# MUL.net
KiCad netlist of a schematic drawn in EAGLE
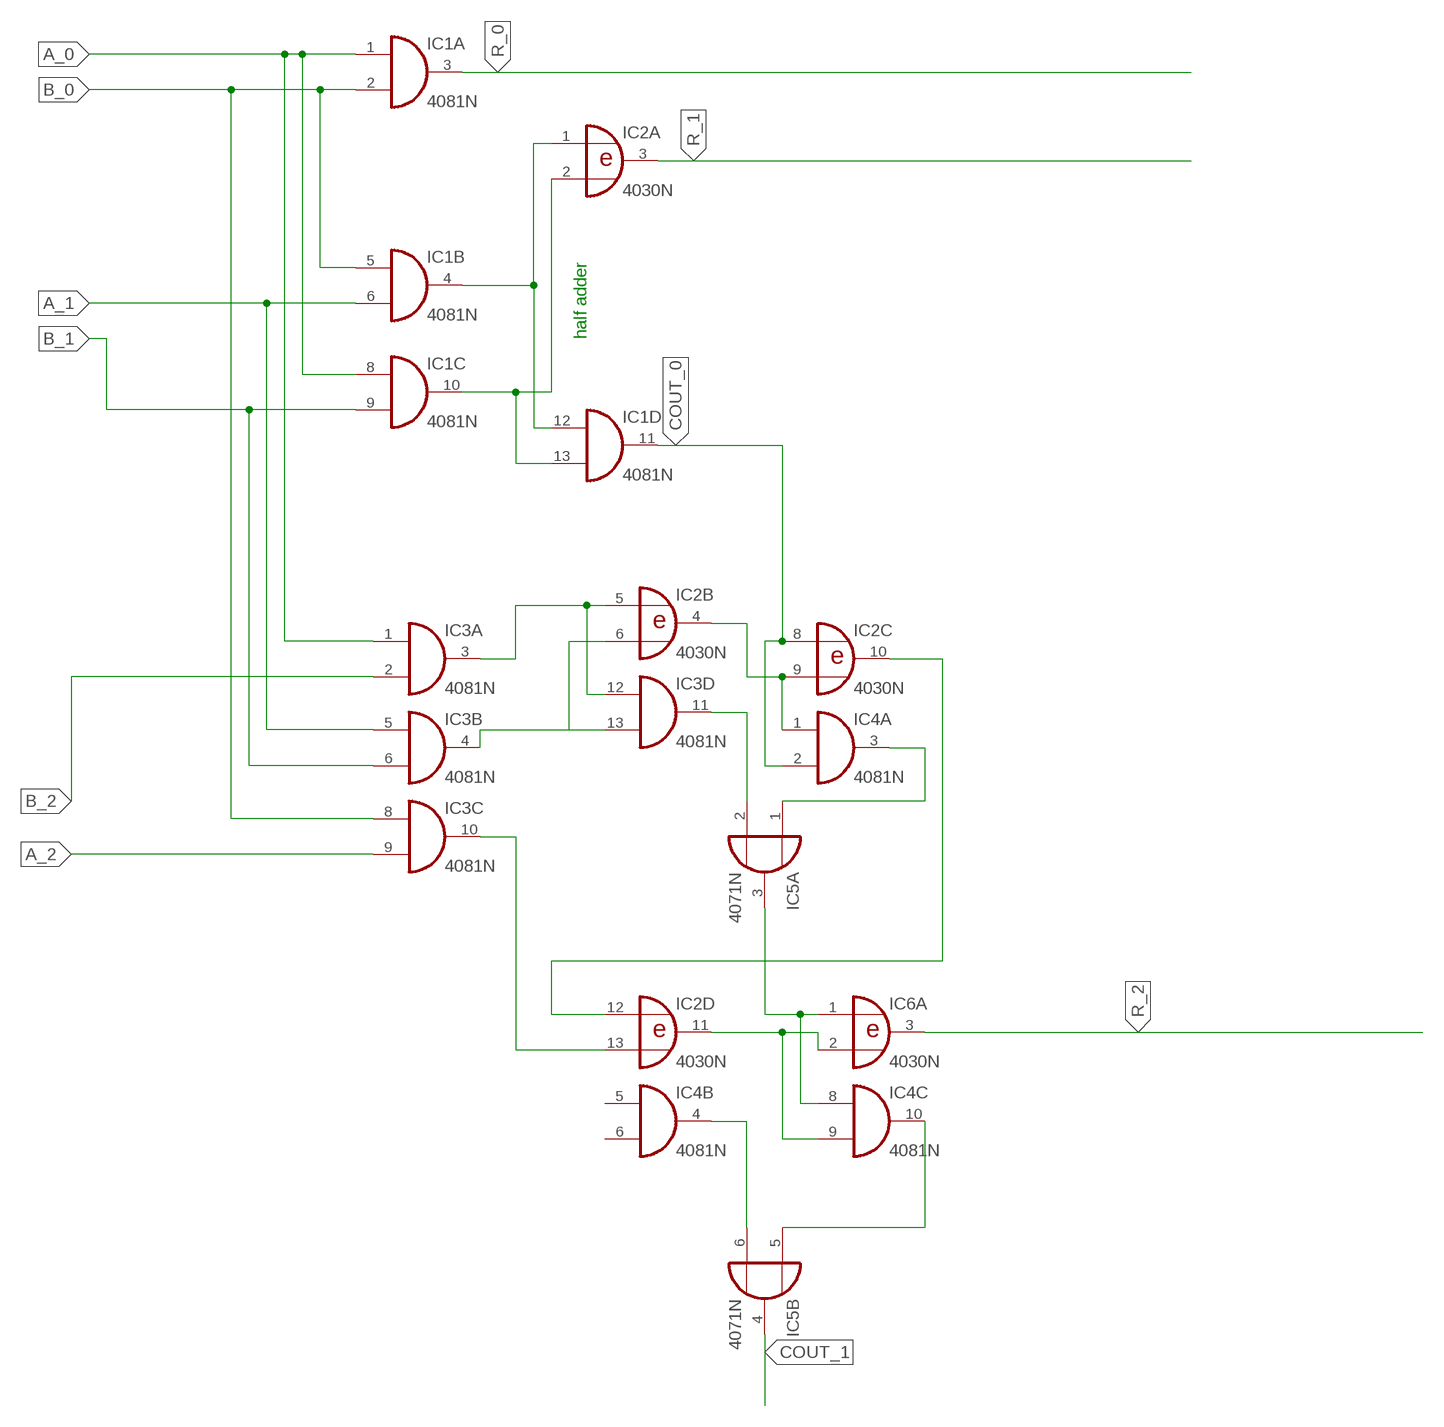
[diagram p0: schematic, sheet 1]

(export (version "E")
  (design (tool "Eeschema 10.0.6"))
  (components
    (comp (ref "IC1")
      (value "4081N")
      (footprint "eagle-import:DIL14")
      (libsource (lib "eagle-import") (part "4081N"))
    )
    (comp (ref "IC2")
      (value "4030N")
      (footprint "eagle-import:DIL14")
      (libsource (lib "eagle-import") (part "4030N"))
    )
    (comp (ref "IC3")
      (value "4081N")
      (footprint "eagle-import:DIL14")
      (libsource (lib "eagle-import") (part "4081N"))
    )
    (comp (ref "IC4")
      (value "4081N")
      (footprint "eagle-import:DIL14")
      (libsource (lib "eagle-import") (part "4081N"))
    )
    (comp (ref "IC5")
      (value "4071N")
      (footprint "eagle-import:DIL14")
      (libsource (lib "eagle-import") (part "4071N"))
    )
    (comp (ref "IC6")
      (value "4030N")
      (footprint "eagle-import:DIL14")
      (libsource (lib "eagle-import") (part "4030N"))
    )
  )
  (nets
    (net (code "1") (name "A_0") (class "Default")
      (node (ref "IC1") (pin "1") (pinfunction "I0_1") (pintype "input"))
      (node (ref "IC1") (pin "8") (pinfunction "I0_8") (pintype "input"))
      (node (ref "IC3") (pin "1") (pinfunction "I0_1") (pintype "input"))
    )
    (net (code "2") (name "A_1") (class "Default")
      (node (ref "IC1") (pin "6") (pinfunction "I1_6") (pintype "input"))
      (node (ref "IC3") (pin "5") (pinfunction "I0_5") (pintype "input"))
    )
    (net (code "3") (name "A_2") (class "Default")
      (node (ref "IC3") (pin "9") (pinfunction "I1_9") (pintype "input"))
    )
    (net (code "4") (name "B_0") (class "Default")
      (node (ref "IC1") (pin "2") (pinfunction "I1_2") (pintype "input"))
      (node (ref "IC1") (pin "5") (pinfunction "I0_5") (pintype "input"))
      (node (ref "IC3") (pin "8") (pinfunction "I0_8") (pintype "input"))
    )
    (net (code "5") (name "B_1") (class "Default")
      (node (ref "IC1") (pin "9") (pinfunction "I1_9") (pintype "input"))
      (node (ref "IC3") (pin "6") (pinfunction "I1_6") (pintype "input"))
    )
    (net (code "6") (name "B_2") (class "Default")
      (node (ref "IC3") (pin "2") (pinfunction "I1_2") (pintype "input"))
    )
    (net (code "7") (name "COUT_0") (class "Default")
      (node (ref "IC1") (pin "11") (pinfunction "O_11") (pintype "output"))
      (node (ref "IC2") (pin "8") (pinfunction "I0_8") (pintype "input"))
      (node (ref "IC4") (pin "2") (pinfunction "I1_2") (pintype "input"))
    )
    (net (code "8") (name "COUT_1") (class "Default")
      (node (ref "IC5") (pin "4") (pinfunction "O_4") (pintype "output"))
    )
    (net (code "9") (name "Net-(IC1B-O)") (class "Default")
      (node (ref "IC1") (pin "12") (pinfunction "I0_12") (pintype "input"))
      (node (ref "IC1") (pin "4") (pinfunction "O_4") (pintype "output"))
      (node (ref "IC2") (pin "1") (pinfunction "I0_1") (pintype "input"))
    )
    (net (code "10") (name "Net-(IC1C-O)") (class "Default")
      (node (ref "IC1") (pin "10") (pinfunction "O_10") (pintype "output"))
      (node (ref "IC1") (pin "13") (pinfunction "I1_13") (pintype "input"))
      (node (ref "IC2") (pin "2") (pinfunction "I1_2") (pintype "input"))
    )
    (net (code "11") (name "Net-(IC2B-I0)") (class "Default")
      (node (ref "IC2") (pin "5") (pinfunction "I0_5") (pintype "input"))
      (node (ref "IC3") (pin "12") (pinfunction "I0_12") (pintype "input"))
      (node (ref "IC3") (pin "3") (pinfunction "O_3") (pintype "output"))
    )
    (net (code "12") (name "Net-(IC2B-I1)") (class "Default")
      (node (ref "IC2") (pin "6") (pinfunction "I1_6") (pintype "input"))
      (node (ref "IC3") (pin "13") (pinfunction "I1_13") (pintype "input"))
      (node (ref "IC3") (pin "4") (pinfunction "O_4") (pintype "output"))
    )
    (net (code "13") (name "Net-(IC2B-O)") (class "Default")
      (node (ref "IC2") (pin "4") (pinfunction "O_4") (pintype "output"))
      (node (ref "IC2") (pin "9") (pinfunction "I1_9") (pintype "input"))
      (node (ref "IC4") (pin "1") (pinfunction "I0_1") (pintype "input"))
    )
    (net (code "14") (name "Net-(IC2C-O)") (class "Default")
      (node (ref "IC2") (pin "10") (pinfunction "O_10") (pintype "output"))
      (node (ref "IC2") (pin "12") (pinfunction "I0_12") (pintype "input"))
    )
    (net (code "15") (name "Net-(IC2D-I1)") (class "Default")
      (node (ref "IC2") (pin "13") (pinfunction "I1_13") (pintype "input"))
      (node (ref "IC3") (pin "10") (pinfunction "O_10") (pintype "output"))
    )
    (net (code "16") (name "Net-(IC2D-O)") (class "Default")
      (node (ref "IC2") (pin "11") (pinfunction "O_11") (pintype "output"))
      (node (ref "IC4") (pin "9") (pinfunction "I1_9") (pintype "input"))
      (node (ref "IC6") (pin "2") (pinfunction "I1_2") (pintype "input"))
    )
    (net (code "17") (name "Net-(IC3D-O)") (class "Default")
      (node (ref "IC3") (pin "11") (pinfunction "O_11") (pintype "output"))
      (node (ref "IC5") (pin "2") (pinfunction "I1_2") (pintype "input"))
    )
    (net (code "18") (name "Net-(IC4A-O)") (class "Default")
      (node (ref "IC4") (pin "3") (pinfunction "O_3") (pintype "output"))
      (node (ref "IC5") (pin "1") (pinfunction "I0_1") (pintype "input"))
    )
    (net (code "19") (name "Net-(IC4B-O)") (class "Default")
      (node (ref "IC4") (pin "4") (pinfunction "O_4") (pintype "output"))
      (node (ref "IC5") (pin "6") (pinfunction "I1_6") (pintype "input"))
    )
    (net (code "20") (name "Net-(IC4C-I0)") (class "Default")
      (node (ref "IC4") (pin "8") (pinfunction "I0_8") (pintype "input"))
      (node (ref "IC5") (pin "3") (pinfunction "O_3") (pintype "output"))
      (node (ref "IC6") (pin "1") (pinfunction "I0_1") (pintype "input"))
    )
    (net (code "21") (name "Net-(IC4C-O)") (class "Default")
      (node (ref "IC4") (pin "10") (pinfunction "O_10") (pintype "output"))
      (node (ref "IC5") (pin "5") (pinfunction "I0_5") (pintype "input"))
    )
    (net (code "22") (name "R_0") (class "Default")
      (node (ref "IC1") (pin "3") (pinfunction "O_3") (pintype "output"))
    )
    (net (code "23") (name "R_1") (class "Default")
      (node (ref "IC2") (pin "3") (pinfunction "O_3") (pintype "output"))
    )
    (net (code "24") (name "R_2") (class "Default")
      (node (ref "IC6") (pin "3") (pinfunction "O_3") (pintype "output"))
    )
    (net (code "25") (name "unconnected-(IC4B-I0-Pad5)") (class "Default")
      (node (ref "IC4") (pin "5") (pinfunction "I0_5") (pintype "input"))
    )
    (net (code "26") (name "unconnected-(IC4B-I1-Pad6)") (class "Default")
      (node (ref "IC4") (pin "6") (pinfunction "I1_6") (pintype "input"))
    )
  )
)
